# VCO_BFR92_sh.net
KiCad netlist of a schematic drawn in Altium Designer
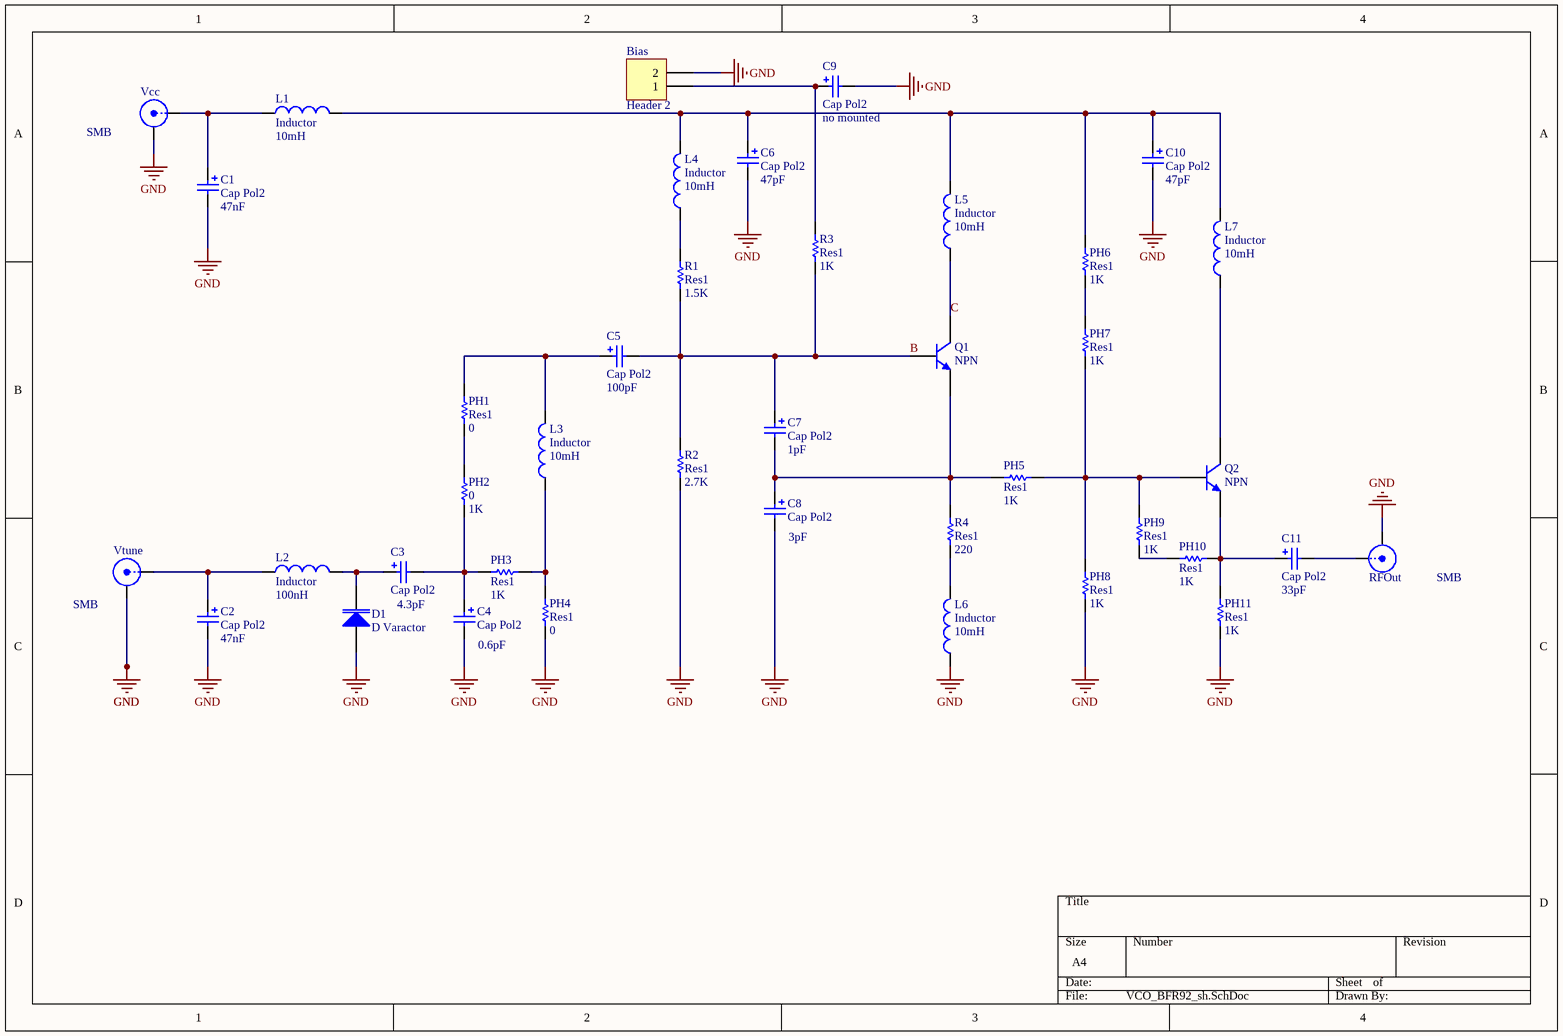
[diagram p0: VCO_BFR92_sh.SchDoc]

(export (version "E")
  (design (tool "Eeschema 10.0.6"))
  (components
    (comp (ref "Bias")
      (value "Header 2")
      (footprint "HDR1X2")
      (description "Header, 2-Pin")
      (fields (field (name "PUBLISHER") "Altium Limited"))
      (libsource (lib "Miscellaneous Connectors") (part "Header 2"))
    )
    (comp (ref "C1")
      (value "Cap Pol2")
      (footprint "6-0805_N")
      (description "Polarized Capacitor (Axial)")
      (fields (field (name "ALTIUM_VALUE") "47nF") (field (name "PUBLISHER") "Altium Limited"))
      (libsource (lib "Miscellaneous Devices") (part "Cap Pol2"))
    )
    (comp (ref "C2")
      (value "Cap Pol2")
      (footprint "6-0805_N")
      (description "Polarized Capacitor (Axial)")
      (fields (field (name "ALTIUM_VALUE") "47nF") (field (name "PUBLISHER") "Altium Limited"))
      (libsource (lib "Miscellaneous Devices") (part "Cap Pol2"))
    )
    (comp (ref "C3")
      (value "Cap Pol2")
      (footprint "6-0805_N")
      (description "Polarized Capacitor (Axial)")
      (fields (field (name "ALTIUM_VALUE") "4.3pF") (field (name "PUBLISHER") "Altium Limited"))
      (libsource (lib "Miscellaneous Devices") (part "Cap Pol2"))
    )
    (comp (ref "C4")
      (value "Cap Pol2")
      (footprint "6-0805_N")
      (description "Polarized Capacitor (Axial)")
      (fields (field (name "ALTIUM_VALUE") "0.6pF") (field (name "PUBLISHER") "Altium Limited"))
      (libsource (lib "Miscellaneous Devices") (part "Cap Pol2"))
    )
    (comp (ref "C5")
      (value "Cap Pol2")
      (footprint "6-0805_N")
      (description "Polarized Capacitor (Axial)")
      (fields (field (name "ALTIUM_VALUE") "100pF") (field (name "PUBLISHER") "Altium Limited"))
      (libsource (lib "Miscellaneous Devices") (part "Cap Pol2"))
    )
    (comp (ref "C6")
      (value "Cap Pol2")
      (footprint "6-0805_N")
      (description "Polarized Capacitor (Axial)")
      (fields (field (name "ALTIUM_VALUE") "47pF") (field (name "PUBLISHER") "Altium Limited"))
      (libsource (lib "Miscellaneous Devices") (part "Cap Pol2"))
    )
    (comp (ref "C7")
      (value "Cap Pol2")
      (footprint "6-0805_N")
      (description "Polarized Capacitor (Axial)")
      (fields (field (name "ALTIUM_VALUE") "1pF") (field (name "PUBLISHER") "Altium Limited"))
      (libsource (lib "Miscellaneous Devices") (part "Cap Pol2"))
    )
    (comp (ref "C8")
      (value "Cap Pol2")
      (footprint "6-0805_N")
      (description "Polarized Capacitor (Axial)")
      (fields (field (name "ALTIUM_VALUE") "3pF") (field (name "PUBLISHER") "Altium Limited"))
      (libsource (lib "Miscellaneous Devices") (part "Cap Pol2"))
    )
    (comp (ref "C9")
      (value "Cap Pol2")
      (footprint "6-0805_N")
      (description "Polarized Capacitor (Axial)")
      (fields (field (name "ALTIUM_VALUE") "no mounted") (field (name "PUBLISHER") "Altium Limited"))
      (libsource (lib "Miscellaneous Devices") (part "Cap Pol2"))
    )
    (comp (ref "C10")
      (value "Cap Pol2")
      (footprint "6-0805_N")
      (description "Polarized Capacitor (Axial)")
      (fields (field (name "ALTIUM_VALUE") "47pF") (field (name "PUBLISHER") "Altium Limited"))
      (libsource (lib "Miscellaneous Devices") (part "Cap Pol2"))
    )
    (comp (ref "C11")
      (value "Cap Pol2")
      (footprint "6-0805_N")
      (description "Polarized Capacitor (Axial)")
      (fields (field (name "ALTIUM_VALUE") "33pF") (field (name "PUBLISHER") "Altium Limited"))
      (libsource (lib "Miscellaneous Devices") (part "Cap Pol2"))
    )
    (comp (ref "D1")
      (value "D Varactor")
      (footprint "6-0805_N")
      (description "Variable Capacitance Diode")
      (fields (field (name "PUBLISHER") "Altium Limited"))
      (libsource (lib "PCB_Project") (part "D Varactor"))
    )
    (comp (ref "L1")
      (value "Inductor")
      (footprint "6-0805_N")
      (fields (field (name "ALTIUM_VALUE") "10mH") (field (name "PUBLISHER") "Altium Limited"))
      (libsource (lib "Miscellaneous Devices") (part "Inductor"))
    )
    (comp (ref "L2")
      (value "Inductor")
      (footprint "6-0805_N")
      (fields (field (name "ALTIUM_VALUE") "100nH") (field (name "PUBLISHER") "Altium Limited"))
      (libsource (lib "Miscellaneous Devices") (part "Inductor"))
    )
    (comp (ref "L3")
      (value "Inductor")
      (footprint "6-0805_N")
      (fields (field (name "ALTIUM_VALUE") "10mH") (field (name "PUBLISHER") "Altium Limited"))
      (libsource (lib "Miscellaneous Devices") (part "Inductor"))
    )
    (comp (ref "L4")
      (value "Inductor")
      (footprint "6-0805_N")
      (fields (field (name "ALTIUM_VALUE") "10mH") (field (name "PUBLISHER") "Altium Limited"))
      (libsource (lib "Miscellaneous Devices") (part "Inductor"))
    )
    (comp (ref "L5")
      (value "Inductor")
      (footprint "6-0805_N")
      (fields (field (name "ALTIUM_VALUE") "10mH") (field (name "PUBLISHER") "Altium Limited"))
      (libsource (lib "Miscellaneous Devices") (part "Inductor"))
    )
    (comp (ref "L6")
      (value "Inductor")
      (footprint "6-0805_N")
      (fields (field (name "ALTIUM_VALUE") "10mH") (field (name "PUBLISHER") "Altium Limited"))
      (libsource (lib "Miscellaneous Devices") (part "Inductor"))
    )
    (comp (ref "L7")
      (value "Inductor")
      (footprint "6-0805_N")
      (fields (field (name "ALTIUM_VALUE") "10mH") (field (name "PUBLISHER") "Altium Limited"))
      (libsource (lib "Miscellaneous Devices") (part "Inductor"))
    )
    (comp (ref "PH1")
      (value "Res1")
      (footprint "6-0805_N")
      (description "Resistor")
      (fields (field (name "ALTIUM_VALUE") "0") (field (name "PUBLISHER") "Altium Limited"))
      (libsource (lib "Miscellaneous Devices") (part "Res1"))
    )
    (comp (ref "PH2")
      (value "0")
      (footprint "6-0805_N")
      (description "Resistor")
      (fields (field (name "ALTIUM_VALUE") "1K") (field (name "PUBLISHER") "Altium Limited"))
      (libsource (lib "Miscellaneous Devices") (part "Res1"))
    )
    (comp (ref "PH3")
      (value "Res1")
      (footprint "6-0805_N")
      (description "Resistor")
      (fields (field (name "ALTIUM_VALUE") "1K") (field (name "PUBLISHER") "Altium Limited"))
      (libsource (lib "Miscellaneous Devices") (part "Res1"))
    )
    (comp (ref "PH4")
      (value "Res1")
      (footprint "6-0805_N")
      (description "Resistor")
      (fields (field (name "ALTIUM_VALUE") "0") (field (name "PUBLISHER") "Altium Limited"))
      (libsource (lib "Miscellaneous Devices") (part "Res1"))
    )
    (comp (ref "PH5")
      (value "Res1")
      (footprint "6-0805_N")
      (description "Resistor")
      (fields (field (name "ALTIUM_VALUE") "1K") (field (name "PUBLISHER") "Altium Limited"))
      (libsource (lib "Miscellaneous Devices") (part "Res1"))
    )
    (comp (ref "PH6")
      (value "Res1")
      (footprint "6-0805_N")
      (description "Resistor")
      (fields (field (name "ALTIUM_VALUE") "1K") (field (name "PUBLISHER") "Altium Limited"))
      (libsource (lib "Miscellaneous Devices") (part "Res1"))
    )
    (comp (ref "PH7")
      (value "Res1")
      (footprint "6-0805_N")
      (description "Resistor")
      (fields (field (name "ALTIUM_VALUE") "1K") (field (name "PUBLISHER") "Altium Limited"))
      (libsource (lib "Miscellaneous Devices") (part "Res1"))
    )
    (comp (ref "PH8")
      (value "Res1")
      (footprint "6-0805_N")
      (description "Resistor")
      (fields (field (name "ALTIUM_VALUE") "1K") (field (name "PUBLISHER") "Altium Limited"))
      (libsource (lib "Miscellaneous Devices") (part "Res1"))
    )
    (comp (ref "PH9")
      (value "Res1")
      (footprint "6-0805_N")
      (description "Resistor")
      (fields (field (name "ALTIUM_VALUE") "1K") (field (name "PUBLISHER") "Altium Limited"))
      (libsource (lib "Miscellaneous Devices") (part "Res1"))
    )
    (comp (ref "PH10")
      (value "Res1")
      (footprint "6-0805_N")
      (description "Resistor")
      (fields (field (name "ALTIUM_VALUE") "1K") (field (name "PUBLISHER") "Altium Limited"))
      (libsource (lib "Miscellaneous Devices") (part "Res1"))
    )
    (comp (ref "PH11")
      (value "Res1")
      (footprint "6-0805_N")
      (description "Resistor")
      (fields (field (name "ALTIUM_VALUE") "1K") (field (name "PUBLISHER") "Altium Limited"))
      (libsource (lib "Miscellaneous Devices") (part "Res1"))
    )
    (comp (ref "Q1")
      (value "NPN")
      (footprint "SOT23_N")
      (description "NPN Bipolar Transistor")
      (fields (field (name "PUBLISHER") "Altium Limited"))
      (libsource (lib "PCB_Project") (part "NPN"))
    )
    (comp (ref "Q2")
      (value "NPN")
      (footprint "SOT23_N")
      (description "NPN Bipolar Transistor")
      (fields (field (name "PUBLISHER") "Altium Limited"))
      (libsource (lib "PCB_Project") (part "NPN"))
    )
    (comp (ref "R1")
      (value "Res1")
      (footprint "6-0805_N")
      (description "Resistor")
      (fields (field (name "ALTIUM_VALUE") "1.5K") (field (name "PUBLISHER") "Altium Limited"))
      (libsource (lib "Miscellaneous Devices") (part "Res1"))
    )
    (comp (ref "R2")
      (value "Res1")
      (footprint "6-0805_N")
      (description "Resistor")
      (fields (field (name "ALTIUM_VALUE") "2.7K") (field (name "PUBLISHER") "Altium Limited"))
      (libsource (lib "Miscellaneous Devices") (part "Res1"))
    )
    (comp (ref "R3")
      (value "Res1")
      (footprint "6-0805_N")
      (description "Resistor")
      (fields (field (name "ALTIUM_VALUE") "1K") (field (name "PUBLISHER") "Altium Limited"))
      (libsource (lib "Miscellaneous Devices") (part "Res1"))
    )
    (comp (ref "R4")
      (value "Res1")
      (footprint "6-0805_N")
      (description "Resistor")
      (fields (field (name "ALTIUM_VALUE") "220") (field (name "PUBLISHER") "Altium Limited"))
      (libsource (lib "Miscellaneous Devices") (part "Res1"))
    )
    (comp (ref "RFOut")
      (value "SMB")
      (footprint "SMA-142-0701-851")
      (description "SMB Straight Connector")
      (fields (field (name "PUBLISHER") "Altium Limited"))
      (libsource (lib "Miscellaneous Connectors") (part "SMB"))
    )
    (comp (ref "Vcc")
      (value "SMB")
      (footprint "SMA-142-0701-851")
      (description "SMB Straight Connector")
      (fields (field (name "PUBLISHER") "Altium Limited"))
      (libsource (lib "Miscellaneous Connectors") (part "SMB"))
    )
    (comp (ref "Vtune")
      (value "SMB")
      (footprint "SMA-142-0701-851")
      (description "SMB Straight Connector")
      (fields (field (name "PUBLISHER") "Altium Limited"))
      (libsource (lib "Miscellaneous Connectors") (part "SMB"))
    )
  )
  (nets
    (net (code "1") (name "/B") (class "Default")
      (node (ref "C5") (pin "2") (pinfunction "2_2") (pintype "passive"))
      (node (ref "C7") (pin "1") (pinfunction "1_1") (pintype "passive"))
      (node (ref "Q1") (pin "3") (pinfunction "B_3") (pintype "passive"))
      (node (ref "R1") (pin "1") (pinfunction "1_1") (pintype "passive"))
      (node (ref "R2") (pin "2") (pinfunction "2_2") (pintype "passive"))
      (node (ref "R3") (pin "1") (pinfunction "1_1") (pintype "passive"))
    )
    (net (code "2") (name "/C") (class "Default")
      (node (ref "L5") (pin "1") (pinfunction "1_1") (pintype "passive"))
      (node (ref "Q1") (pin "1") (pinfunction "C_1") (pintype "passive"))
    )
    (net (code "3") (name "GND") (class "Default")
      (node (ref "Bias") (pin "2") (pinfunction "2_2") (pintype "passive"))
      (node (ref "C1") (pin "2") (pinfunction "2_2") (pintype "passive"))
      (node (ref "C10") (pin "2") (pinfunction "2_2") (pintype "passive"))
      (node (ref "C2") (pin "2") (pinfunction "2_2") (pintype "passive"))
      (node (ref "C4") (pin "2") (pinfunction "2_2") (pintype "passive"))
      (node (ref "C6") (pin "2") (pinfunction "2_2") (pintype "passive"))
      (node (ref "C8") (pin "2") (pinfunction "2_2") (pintype "passive"))
      (node (ref "C9") (pin "2") (pinfunction "2_2") (pintype "passive"))
      (node (ref "D1") (pin "2") (pinfunction "A_2") (pintype "passive"))
      (node (ref "L6") (pin "1") (pinfunction "1_1") (pintype "passive"))
      (node (ref "PH11") (pin "2") (pinfunction "2_2") (pintype "passive"))
      (node (ref "PH4") (pin "1") (pinfunction "1_1") (pintype "passive"))
      (node (ref "PH8") (pin "1") (pinfunction "1_1") (pintype "passive"))
      (node (ref "R2") (pin "1") (pinfunction "1_1") (pintype "passive"))
      (node (ref "RFOut") (pin "2") (pinfunction "Y_2") (pintype "passive"))
      (node (ref "Vcc") (pin "2") (pinfunction "Y_2") (pintype "passive"))
      (node (ref "Vtune") (pin "2") (pinfunction "Y_2") (pintype "passive"))
    )
    (net (code "4") (name "Net-(Bias-Pad1)") (class "Default")
      (node (ref "Bias") (pin "1") (pinfunction "1_1") (pintype "passive"))
      (node (ref "C9") (pin "1") (pinfunction "1_1") (pintype "passive"))
      (node (ref "R3") (pin "2") (pinfunction "2_2") (pintype "passive"))
    )
    (net (code "5") (name "Net-(C3-Pad2)") (class "Default")
      (node (ref "C3") (pin "2") (pinfunction "2_2") (pintype "passive"))
      (node (ref "C4") (pin "1") (pinfunction "1_1") (pintype "passive"))
      (node (ref "PH2") (pin "1") (pinfunction "1_1") (pintype "passive"))
      (node (ref "PH3") (pin "2") (pinfunction "2_2") (pintype "passive"))
    )
    (net (code "6") (name "Net-(C5-Pad1)") (class "Default")
      (node (ref "C5") (pin "1") (pinfunction "1_1") (pintype "passive"))
      (node (ref "L3") (pin "2") (pinfunction "2_2") (pintype "passive"))
      (node (ref "PH1") (pin "2") (pinfunction "2_2") (pintype "passive"))
    )
    (net (code "7") (name "Net-(C10-Pad1)") (class "Default")
      (node (ref "C10") (pin "1") (pinfunction "1_1") (pintype "passive"))
      (node (ref "C6") (pin "1") (pinfunction "1_1") (pintype "passive"))
      (node (ref "L1") (pin "2") (pinfunction "2_2") (pintype "passive"))
      (node (ref "L4") (pin "2") (pinfunction "2_2") (pintype "passive"))
      (node (ref "L5") (pin "2") (pinfunction "2_2") (pintype "passive"))
      (node (ref "L7") (pin "2") (pinfunction "2_2") (pintype "passive"))
      (node (ref "PH6") (pin "2") (pinfunction "2_2") (pintype "passive"))
    )
    (net (code "8") (name "Net-(D1-K)") (class "Default")
      (node (ref "C3") (pin "1") (pinfunction "1_1") (pintype "passive"))
      (node (ref "D1") (pin "1") (pinfunction "K_1") (pintype "passive"))
      (node (ref "L2") (pin "2") (pinfunction "2_2") (pintype "passive"))
    )
    (net (code "9") (name "Net-(L3-Pad1)") (class "Default")
      (node (ref "L3") (pin "1") (pinfunction "1_1") (pintype "passive"))
      (node (ref "PH3") (pin "1") (pinfunction "1_1") (pintype "passive"))
      (node (ref "PH4") (pin "2") (pinfunction "2_2") (pintype "passive"))
    )
    (net (code "10") (name "Net-(L4-Pad1)") (class "Default")
      (node (ref "L4") (pin "1") (pinfunction "1_1") (pintype "passive"))
      (node (ref "R1") (pin "2") (pinfunction "2_2") (pintype "passive"))
    )
    (net (code "11") (name "Net-(L6-Pad2)") (class "Default")
      (node (ref "L6") (pin "2") (pinfunction "2_2") (pintype "passive"))
      (node (ref "R4") (pin "1") (pinfunction "1_1") (pintype "passive"))
    )
    (net (code "12") (name "Net-(PH1-Pad1)") (class "Default")
      (node (ref "PH1") (pin "1") (pinfunction "1_1") (pintype "passive"))
      (node (ref "PH2") (pin "2") (pinfunction "2_2") (pintype "passive"))
    )
    (net (code "13") (name "Net-(PH6-Pad1)") (class "Default")
      (node (ref "PH6") (pin "1") (pinfunction "1_1") (pintype "passive"))
      (node (ref "PH7") (pin "2") (pinfunction "2_2") (pintype "passive"))
    )
    (net (code "14") (name "Net-(PH10-Pad2)") (class "Default")
      (node (ref "PH10") (pin "2") (pinfunction "2_2") (pintype "passive"))
      (node (ref "PH9") (pin "2") (pinfunction "2_2") (pintype "passive"))
    )
    (net (code "15") (name "Net-(Q1-E)") (class "Default")
      (node (ref "C7") (pin "2") (pinfunction "2_2") (pintype "passive"))
      (node (ref "C8") (pin "1") (pinfunction "1_1") (pintype "passive"))
      (node (ref "PH5") (pin "2") (pinfunction "2_2") (pintype "passive"))
      (node (ref "Q1") (pin "2") (pinfunction "E_2") (pintype "passive"))
      (node (ref "R4") (pin "2") (pinfunction "2_2") (pintype "passive"))
    )
    (net (code "16") (name "Net-(Q2-B)") (class "Default")
      (node (ref "PH5") (pin "1") (pinfunction "1_1") (pintype "passive"))
      (node (ref "PH7") (pin "1") (pinfunction "1_1") (pintype "passive"))
      (node (ref "PH8") (pin "2") (pinfunction "2_2") (pintype "passive"))
      (node (ref "PH9") (pin "1") (pinfunction "1_1") (pintype "passive"))
      (node (ref "Q2") (pin "3") (pinfunction "B_3") (pintype "passive"))
    )
    (net (code "17") (name "Net-(Q2-C)") (class "Default")
      (node (ref "L7") (pin "1") (pinfunction "1_1") (pintype "passive"))
      (node (ref "Q2") (pin "1") (pinfunction "C_1") (pintype "passive"))
    )
    (net (code "18") (name "Net-(Q2-E)") (class "Default")
      (node (ref "C11") (pin "1") (pinfunction "1_1") (pintype "passive"))
      (node (ref "PH10") (pin "1") (pinfunction "1_1") (pintype "passive"))
      (node (ref "PH11") (pin "1") (pinfunction "1_1") (pintype "passive"))
      (node (ref "Q2") (pin "2") (pinfunction "E_2") (pintype "passive"))
    )
    (net (code "19") (name "Net-(RFOut-X)") (class "Default")
      (node (ref "C11") (pin "2") (pinfunction "2_2") (pintype "passive"))
      (node (ref "RFOut") (pin "1") (pinfunction "X_1") (pintype "passive"))
    )
    (net (code "20") (name "Net-(Vcc-X)") (class "Default")
      (node (ref "C1") (pin "1") (pinfunction "1_1") (pintype "passive"))
      (node (ref "L1") (pin "1") (pinfunction "1_1") (pintype "passive"))
      (node (ref "Vcc") (pin "1") (pinfunction "X_1") (pintype "passive"))
    )
    (net (code "21") (name "Net-(Vtune-X)") (class "Default")
      (node (ref "C2") (pin "1") (pinfunction "1_1") (pintype "passive"))
      (node (ref "L2") (pin "1") (pinfunction "1_1") (pintype "passive"))
      (node (ref "Vtune") (pin "1") (pinfunction "X_1") (pintype "passive"))
    )
  )
)
